# PWR_PROT.net
KiCad netlist of a schematic drawn in Altium Designer
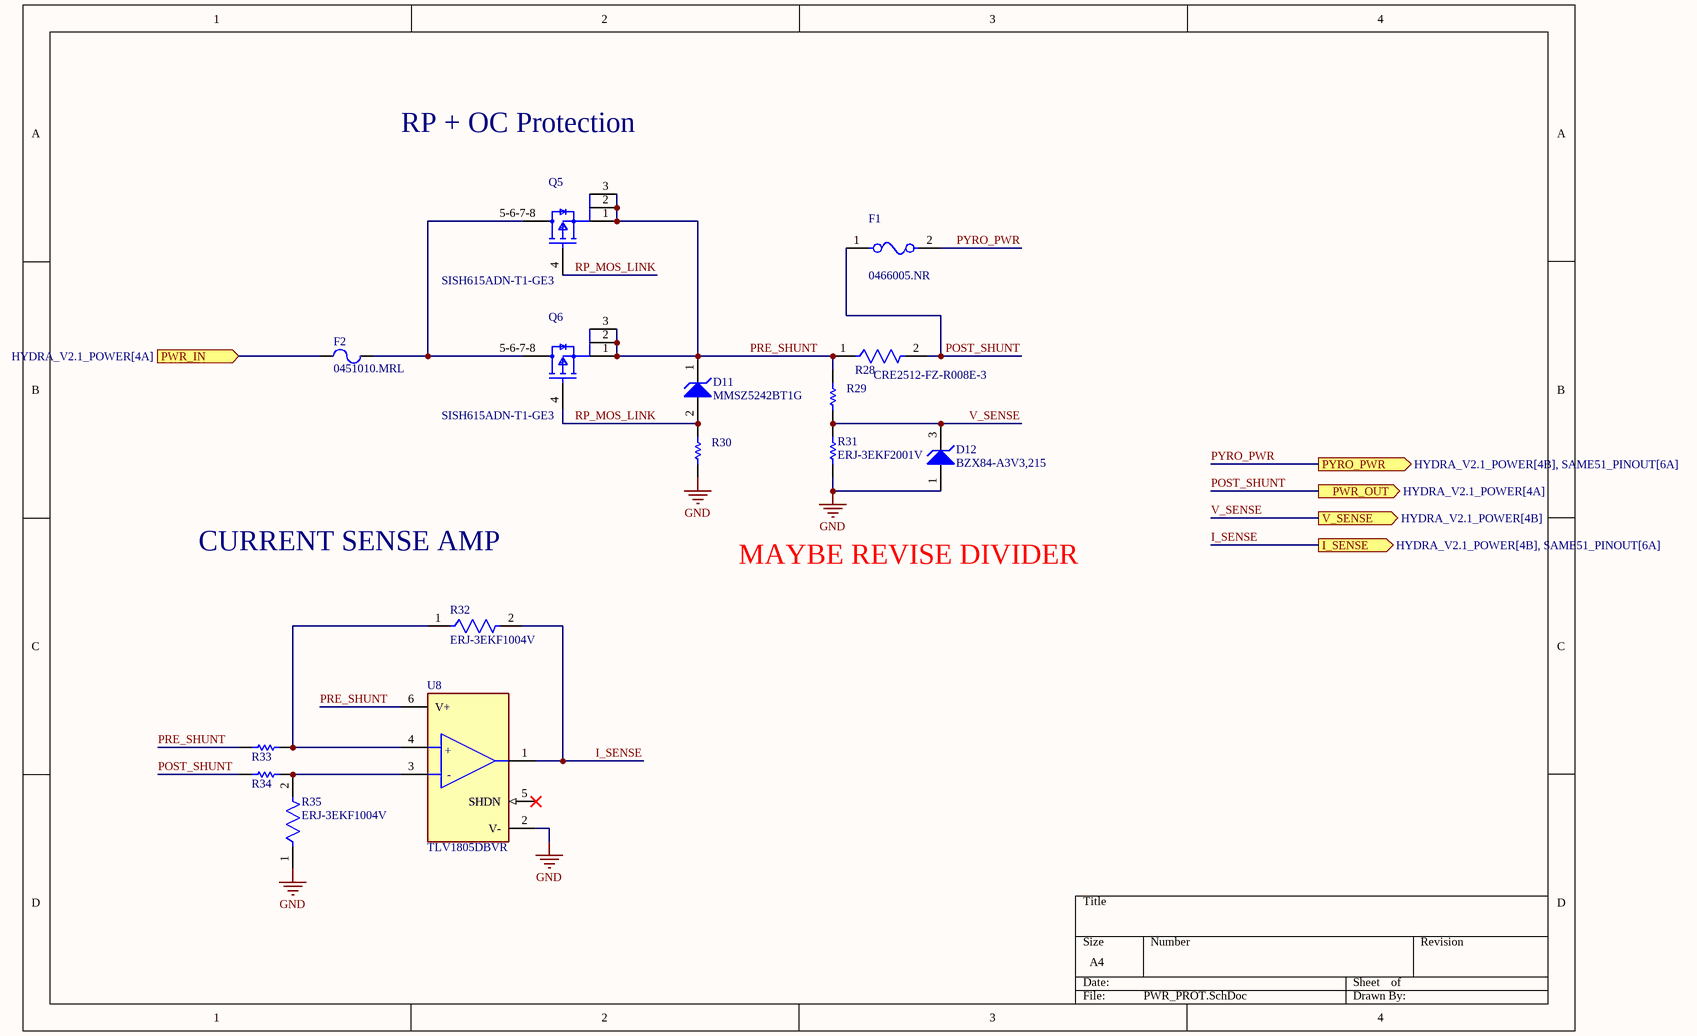
[diagram p0: PWR_PROT.SchDoc]

(export (version "E")
  (design (tool "Eeschema 10.0.6"))
  (components
    (comp (ref "D11")
      (value "MMSZ5242BT1G")
      (footprint "ONSC-SOD-123-2-425-04_V")
      (description "Zener Voltage Regulator, 500 mW, 2-Pin SOD-123, Pb-Free, Tape and Reel")
      (fields (field (name "MANUFACTURER") "On Semiconductor"))
      (libsource (lib "Altium Content Vault") (part "ONSC-K1A2-2"))
    )
    (comp (ref "D12")
      (value "BZX84-A3V3,215")
      (footprint "SOT95P230X110-3N")
      (description "DIODE ZENER 3.3V 250MW SOT23")
      (libsource (lib "uORocketry Hardware") (part "BZX84-A3V3,215"))
    )
    (comp (ref "F1")
      (value "0466005.NR")
      (footprint "FP-0466-MFG")
      (description "FUSE BOARD MNT 5A 32VAC/VDC 1206")
      (fields
        (field (name "OCTOPART") "https://octopart.com/0466005.nr-littelfuse-143206")
        (field (name "MANUFACTURER") "Littelfuse Inc")
      )
      (libsource (lib "Altium Content Vault") (part "5bcf9b9f640e542cf0359d10258e979"))
    )
    (comp (ref "F2")
      (value "0451010.MRL")
      (footprint "LFUS-45X_V")
      (description "Fuse, 125 V, 10 A, -55 to 125 degC, 2-Pin SMD, RoHS, Tape and Reel")
      (fields (field (name "MANUFACTURER") "Littelfuse"))
      (libsource (lib "Altium Content Vault") (part "FUSE-2"))
    )
    (comp (ref "Q5")
      (value "SISH615ADN-T1-GE3")
      (footprint "SISH615ADN-T1-GE3-Footprint-1")
      (description "Trans MOSFET P-CH 20V 22.1A 8-Pin PowerPAK 1212 EP T/R")
      (libsource (lib "uORocketry Hardware") (part "SISH615ADN-T1-GE3-Symbol-1"))
    )
    (comp (ref "Q6")
      (value "SISH615ADN-T1-GE3")
      (footprint "SISH615ADN-T1-GE3-Footprint-1")
      (description "Trans MOSFET P-CH 20V 22.1A 8-Pin PowerPAK 1212 EP T/R")
      (libsource (lib "uORocketry Hardware") (part "SISH615ADN-T1-GE3-Symbol-1"))
    )
    (comp (ref "R28")
      (value "CRE2512-FZ-R008E-3")
      (footprint "CRF2512-FZ-R005ELF-Footprint-1")
      (description "Actually https://www.digikey.ca/en/products/detail/bourns-inc/CRE2512-FZ-R008E-3/4900057")
      (libsource (lib "uORocketry Hardware") (part "CRF2512-FZ-R005ELF"))
    )
    (comp (ref "R29")
      (value "ERJ3EKF1002V")
      (footprint "RESC1609X55X30LL15T15")
      (description "Chip Resistor, 10 KOhm, +/- 1%, 0.1 W, -55 to 155 degC, 0603 (1608 Metric), RoHS, Tape and Reel")
      (fields (field (name "TOLERANCE") "1%") (field (name "MANUFACTURER") "Panasonic"))
      (libsource (lib "Altium Content Vault") (part "RES-2"))
    )
    (comp (ref "R30")
      (value "ERJ3EKF1002V")
      (footprint "RESC1609X55X30LL15T15")
      (description "Chip Resistor, 10 KOhm, +/- 1%, 0.1 W, -55 to 155 degC, 0603 (1608 Metric), RoHS, Tape and Reel")
      (fields (field (name "TOLERANCE") "1%") (field (name "MANUFACTURER") "Panasonic"))
      (libsource (lib "Altium Content Vault") (part "RES-2"))
    )
    (comp (ref "R31")
      (value "ERJ-3EKF2001V")
      (footprint "RESC1608X55X30ML15T15")
      (fields (field (name "MANUFACTURER") "Panasonic"))
      (libsource (lib "Altium Content Vault") (part "RES"))
    )
    (comp (ref "R32")
      (value "ERJ-3EKF1004V")
      (footprint "FP-ERJ3EK-IPC_C")
      (description "RES SMD 1M OHM 1% 1/10W 0603")
      (fields (field (name "TOLERANCE") "1%"))
      (libsource (lib "Altium Content Vault") (part "1029c3af85768c4190bb7ad29bc67b5"))
    )
    (comp (ref "R33")
      (value "ERJ3EKF1002V")
      (footprint "RESC1609X55X30LL15T15")
      (description "Chip Resistor, 10 KOhm, +/- 1%, 0.1 W, -55 to 155 degC, 0603 (1608 Metric), RoHS, Tape and Reel")
      (fields (field (name "TOLERANCE") "1%") (field (name "MANUFACTURER") "Panasonic"))
      (libsource (lib "Altium Content Vault") (part "RES-2"))
    )
    (comp (ref "R34")
      (value "ERJ3EKF1002V")
      (footprint "RESC1609X55X30LL15T15")
      (description "Chip Resistor, 10 KOhm, +/- 1%, 0.1 W, -55 to 155 degC, 0603 (1608 Metric), RoHS, Tape and Reel")
      (fields (field (name "TOLERANCE") "1%") (field (name "MANUFACTURER") "Panasonic"))
      (libsource (lib "Altium Content Vault") (part "RES-2"))
    )
    (comp (ref "R35")
      (value "ERJ-3EKF1004V")
      (footprint "FP-ERJ3EK-IPC_C")
      (description "RES SMD 1M OHM 1% 1/10W 0603")
      (fields (field (name "TOLERANCE") "1%"))
      (libsource (lib "Altium Content Vault") (part "1029c3af85768c4190bb7ad29bc67b5"))
    )
    (comp (ref "U8")
      (value "TLV1805DBVR")
      (footprint "FP-DBV0006A-IPC_C")
      (description "40V, RAIL-TO-RAIL INPUT, PUSH-PU")
      (libsource (lib "Altium Content Vault") (part "c7aa3bc3dbf0dc8b0b0354779bd1228"))
    )
  )
  (nets
    (net (code "1") (name "/I_SENSE") (class "Default")
      (node (ref "R32") (pin "2") (pinfunction "2_2") (pintype "passive"))
      (node (ref "U8") (pin "1") (pinfunction "OUT_1") (pintype "passive"))
    )
    (net (code "2") (name "/POST_SHUNT") (class "Default")
      (node (ref "F1") (pin "1") (pinfunction "1_1") (pintype "passive"))
      (node (ref "R28") (pin "2") (pinfunction "2_2") (pintype "passive"))
      (node (ref "R34") (pin "1") (pinfunction "1_1") (pintype "passive"))
    )
    (net (code "3") (name "/PRE_SHUNT") (class "Default")
      (node (ref "D11") (pin "1") (pinfunction "K_1") (pintype "passive"))
      (node (ref "Q5") (pin "1") (pinfunction "S_1") (pintype "passive"))
      (node (ref "Q5") (pin "2") (pinfunction "S_2") (pintype "passive"))
      (node (ref "Q5") (pin "3") (pinfunction "S_3") (pintype "passive"))
      (node (ref "Q6") (pin "1") (pinfunction "S_1") (pintype "passive"))
      (node (ref "Q6") (pin "2") (pinfunction "S_2") (pintype "passive"))
      (node (ref "Q6") (pin "3") (pinfunction "S_3") (pintype "passive"))
      (node (ref "R28") (pin "1") (pinfunction "1_1") (pintype "passive"))
      (node (ref "R29") (pin "1") (pinfunction "1_1") (pintype "passive"))
      (node (ref "R33") (pin "1") (pinfunction "1_1") (pintype "passive"))
      (node (ref "U8") (pin "6") (pinfunction "V+_6") (pintype "power_in"))
    )
    (net (code "4") (name "/PWR_IN") (class "Default")
      (node (ref "F2") (pin "1") (pinfunction "1_1") (pintype "passive"))
    )
    (net (code "5") (name "/PYRO_PWR") (class "Default")
      (node (ref "F1") (pin "2") (pinfunction "2_2") (pintype "passive"))
    )
    (net (code "6") (name "/RP_MOS_LINK") (class "Default")
      (node (ref "D11") (pin "2") (pinfunction "A_2") (pintype "passive"))
      (node (ref "Q5") (pin "4") (pinfunction "G_4") (pintype "passive"))
      (node (ref "Q6") (pin "4") (pinfunction "G_4") (pintype "passive"))
      (node (ref "R30") (pin "1") (pinfunction "1_1") (pintype "passive"))
    )
    (net (code "7") (name "/V_SENSE") (class "Default")
      (node (ref "D12") (pin "3") (pinfunction "K_3") (pintype "passive"))
      (node (ref "R29") (pin "2") (pinfunction "2_2") (pintype "passive"))
      (node (ref "R31") (pin "2") (pinfunction "2_2") (pintype "passive"))
    )
    (net (code "8") (name "GND") (class "Default")
      (node (ref "D12") (pin "1") (pinfunction "A_1") (pintype "passive"))
      (node (ref "R30") (pin "2") (pinfunction "2_2") (pintype "passive"))
      (node (ref "R31") (pin "1") (pinfunction "1_1") (pintype "passive"))
      (node (ref "R35") (pin "1") (pinfunction "1_1") (pintype "passive"))
      (node (ref "U8") (pin "2") (pinfunction "V-_2") (pintype "power_in"))
    )
    (net (code "9") (name "Net-(Q5-D)") (class "Default")
      (node (ref "F2") (pin "2") (pinfunction "2_2") (pintype "passive"))
      (node (ref "Q5") (pin "5-6-7-8") (pinfunction "D_5-6-7-8") (pintype "passive"))
      (node (ref "Q6") (pin "5-6-7-8") (pinfunction "D_5-6-7-8") (pintype "passive"))
    )
    (net (code "10") (name "Net-(U8-+IN)") (class "Default")
      (node (ref "R32") (pin "1") (pinfunction "1_1") (pintype "passive"))
      (node (ref "R33") (pin "2") (pinfunction "2_2") (pintype "passive"))
      (node (ref "U8") (pin "4") (pinfunction "+IN_4") (pintype "tri_state"))
    )
    (net (code "11") (name "Net-(U8--IN)") (class "Default")
      (node (ref "R34") (pin "2") (pinfunction "2_2") (pintype "passive"))
      (node (ref "R35") (pin "2") (pinfunction "2_2") (pintype "passive"))
      (node (ref "U8") (pin "3") (pinfunction "-IN_3") (pintype "tri_state"))
    )
    (net (code "12") (name "unconnected-(U8-SHDN-Pad5)") (class "Default")
      (node (ref "U8") (pin "5") (pinfunction "SHDN_5") (pintype "input+no_connect"))
    )
  )
)
